# SparkFun_6DoF_ISM330DHCX_Qwiic_Micro_Alt.net
KiCad netlist of a schematic drawn in EAGLE
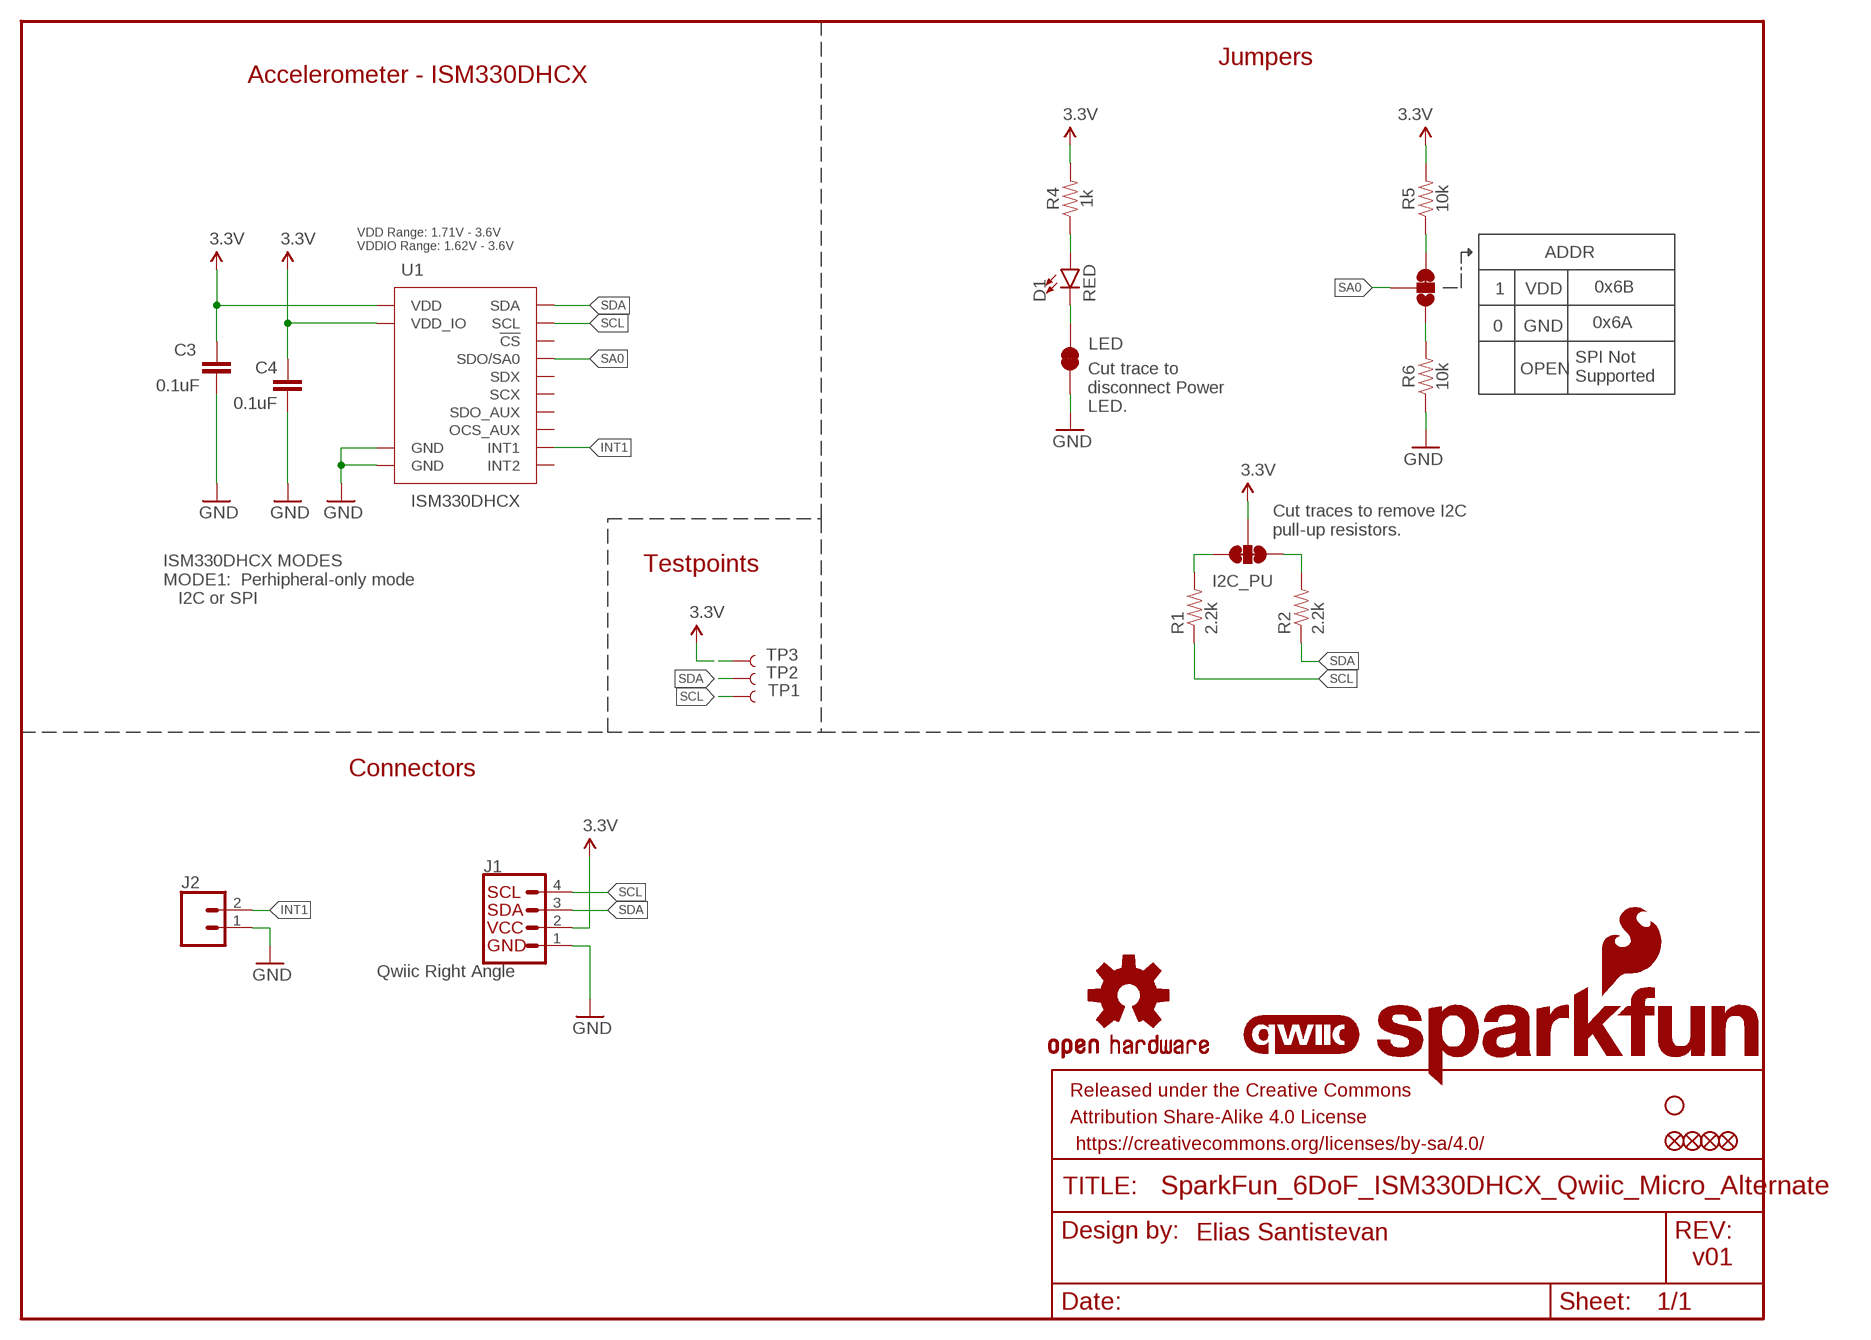
[diagram p0: schematic, sheet 1]

(export (version "E")
  (design (tool "Eeschema 10.0.6"))
  (components
    (comp (ref "ADDR")
      (value "JUMPER-SMT_3_1-NC_TRACE_SILK")
      (footprint "eagle-import:SMT-JUMPER_3_1-NC_TRACE_SILK")
      (libsource (lib "eagle-import") (part "JUMPER-SMT_3_1-NC_TRACE_SILK"))
    )
    (comp (ref "C3")
      (value "0.1uF")
      (footprint "eagle-import:0402-TIGHT")
      (libsource (lib "eagle-import") (part "0.1UF-0402T-6.3V-10%-X7R"))
    )
    (comp (ref "C4")
      (value "0.1uF")
      (footprint "eagle-import:0402-TIGHT")
      (libsource (lib "eagle-import") (part "0.1UF-0402T-6.3V-10%-X7R"))
    )
    (comp (ref "D1")
      (value "RED")
      (footprint "eagle-import:0402-TIGHT")
      (libsource (lib "eagle-import") (part "LED_0402"))
    )
    (comp (ref "FD1")
      (value "FIDUCIALUFIDUCIAL")
      (footprint "eagle-import:FIDUCIAL-MICRO")
      (libsource (lib "eagle-import") (part "FIDUCIALUFIDUCIAL"))
    )
    (comp (ref "FD2")
      (value "FIDUCIALUFIDUCIAL")
      (footprint "eagle-import:FIDUCIAL-MICRO")
      (libsource (lib "eagle-import") (part "FIDUCIALUFIDUCIAL"))
    )
    (comp (ref "FID1")
      (value "FIDUCIALUFIDUCIAL")
      (footprint "eagle-import:FIDUCIAL-MICRO")
      (libsource (lib "eagle-import") (part "FIDUCIALUFIDUCIAL"))
    )
    (comp (ref "FID2")
      (value "FIDUCIALUFIDUCIAL")
      (footprint "eagle-import:FIDUCIAL-MICRO")
      (libsource (lib "eagle-import") (part "FIDUCIALUFIDUCIAL"))
    )
    (comp (ref "FRAME1")
      (value "FRAME-LETTER")
      (footprint "eagle-import:CREATIVE_COMMONS")
      (fields (field (name "DESIGNER") "Elias Santistevan"))
      (libsource (lib "eagle-import") (part "FRAME-LETTER"))
    )
    (comp (ref "I2C_PU")
      (value "S_MODE")
      (footprint "eagle-import:SMT-JUMPER_3_2-NC_TRACE_SILK")
      (libsource (lib "eagle-import") (part "JUMPER-SMT_3_2-NC_TRACE_SILK"))
    )
    (comp (ref "J1")
      (value "Qwiic Right Angle")
      (footprint "eagle-import:JST04_1MM_RA")
      (libsource (lib "eagle-import") (part "I2C_STANDARDQWIIC"))
    )
    (comp (ref "J2")
      (value "CONN_02_1.5MM")
      (footprint "eagle-import:1X02_1.5MM_NO_SILK")
      (libsource (lib "eagle-import") (part "CONN_02_1.5MM"))
    )
    (comp (ref "LED")
      (value "JUMPER-SMT_2_NC_TRACE_SILK")
      (footprint "eagle-import:SMT-JUMPER_2_NC_TRACE_SILK")
      (libsource (lib "eagle-import") (part "JUMPER-SMT_2_NC_TRACE_SILK"))
    )
    (comp (ref "LOGO1")
      (value "QWIIC_LOGO_3MM")
      (footprint "eagle-import:QWIIC_3MM")
      (libsource (lib "eagle-import") (part "QWIIC_LOGO_3MM"))
    )
    (comp (ref "LOGO2")
      (value "OSHW-LOGOMINI")
      (footprint "eagle-import:OSHW-LOGO-MINI")
      (libsource (lib "eagle-import") (part "OSHW-LOGOMINI"))
    )
    (comp (ref "LOGO3")
      (value "SFE_LOGO_NAME_FLAMEBLANK")
      (footprint "eagle-import:BLANK")
      (libsource (lib "eagle-import") (part "SFE_LOGO_NAME_FLAMEBLANK"))
    )
    (comp (ref "R1")
      (value "2.2k")
      (footprint "eagle-import:0402-TIGHT")
      (libsource (lib "eagle-import") (part "2.2KOHM-0402T-1/16W-1%"))
    )
    (comp (ref "R2")
      (value "2.2k")
      (footprint "eagle-import:0402-TIGHT")
      (libsource (lib "eagle-import") (part "2.2KOHM-0402T-1/16W-1%"))
    )
    (comp (ref "R4")
      (value "1k")
      (footprint "eagle-import:0402-TIGHT")
      (libsource (lib "eagle-import") (part "1KOHM-0402T-1/16W-1%"))
    )
    (comp (ref "R5")
      (value "10k")
      (footprint "eagle-import:0402-TIGHT")
      (libsource (lib "eagle-import") (part "10KOHM-0402T-1/16W-1%"))
    )
    (comp (ref "R6")
      (value "10k")
      (footprint "eagle-import:0402-TIGHT")
      (libsource (lib "eagle-import") (part "10KOHM-0402T-1/16W-1%"))
    )
    (comp (ref "STANDOFF1")
      (value "STAND-OFFTIGHT")
      (footprint "eagle-import:STAND-OFF-TIGHT")
      (libsource (lib "eagle-import") (part "STAND-OFFTIGHT"))
    )
    (comp (ref "TP1")
      (value "TEST-POINT3")
      (footprint "eagle-import:PAD.03X.03")
      (libsource (lib "eagle-import") (part "TEST-POINT3"))
    )
    (comp (ref "TP2")
      (value "TEST-POINT3")
      (footprint "eagle-import:PAD.03X.03")
      (libsource (lib "eagle-import") (part "TEST-POINT3"))
    )
    (comp (ref "TP3")
      (value "TEST-POINT3")
      (footprint "eagle-import:PAD.03X.03")
      (libsource (lib "eagle-import") (part "TEST-POINT3"))
    )
    (comp (ref "U1")
      (value "ISM330DHCX")
      (footprint "eagle-import:LGA-14L")
      (libsource (lib "eagle-import") (part "ISM330DHCX"))
    )
  )
  (nets
    (net (code "1") (name "3.3V") (class "Default")
      (node (ref "C3") (pin "1") (pinfunction "1_1") (pintype "passive"))
      (node (ref "C4") (pin "1") (pinfunction "1_1") (pintype "passive"))
      (node (ref "I2C_PU") (pin "2") (pinfunction "2_2") (pintype "passive"))
      (node (ref "J1") (pin "2") (pinfunction "2_2") (pintype "power_in"))
      (node (ref "R4") (pin "2") (pinfunction "2_2") (pintype "passive"))
      (node (ref "R5") (pin "2") (pinfunction "2_2") (pintype "passive"))
      (node (ref "TP3") (pin "1") (pinfunction "1_1") (pintype "bidirectional"))
      (node (ref "U1") (pin "P5") (pinfunction "VDD_IO_P5") (pintype "power_in"))
      (node (ref "U1") (pin "P8") (pinfunction "VDD_P8") (pintype "power_in"))
    )
    (net (code "2") (name "GND") (class "Default")
      (node (ref "C3") (pin "2") (pinfunction "2_2") (pintype "passive"))
      (node (ref "C4") (pin "2") (pinfunction "2_2") (pintype "passive"))
      (node (ref "J1") (pin "1") (pinfunction "1_1") (pintype "power_in"))
      (node (ref "J2") (pin "1") (pinfunction "1_1") (pintype "passive"))
      (node (ref "LED") (pin "1") (pinfunction "1_1") (pintype "passive"))
      (node (ref "R6") (pin "1") (pinfunction "1_1") (pintype "passive"))
      (node (ref "U1") (pin "P6") (pinfunction "GND_P6") (pintype "power_in"))
      (node (ref "U1") (pin "P7") (pinfunction "GND_P7") (pintype "power_in"))
    )
    (net (code "3") (name "INT1") (class "Default")
      (node (ref "J2") (pin "2") (pinfunction "2_2") (pintype "passive"))
      (node (ref "U1") (pin "P4") (pinfunction "INT1_P4") (pintype "bidirectional"))
    )
    (net (code "4") (name "Net-(ADDR-Pad1)") (class "Default")
      (node (ref "ADDR") (pin "1") (pinfunction "1_1") (pintype "passive"))
      (node (ref "R6") (pin "2") (pinfunction "2_2") (pintype "passive"))
    )
    (net (code "5") (name "Net-(ADDR-Pad3)") (class "Default")
      (node (ref "ADDR") (pin "3") (pinfunction "3_3") (pintype "passive"))
      (node (ref "R5") (pin "1") (pinfunction "1_1") (pintype "passive"))
    )
    (net (code "6") (name "Net-(D1-PadA)") (class "Default")
      (node (ref "D1") (pin "A") (pinfunction "A_A") (pintype "passive"))
      (node (ref "R4") (pin "1") (pinfunction "1_1") (pintype "passive"))
    )
    (net (code "7") (name "Net-(D1-PadC)") (class "Default")
      (node (ref "D1") (pin "C") (pinfunction "C_C") (pintype "passive"))
      (node (ref "LED") (pin "2") (pinfunction "2_2") (pintype "passive"))
    )
    (net (code "8") (name "Net-(I2C_PU-Pad1)") (class "Default")
      (node (ref "I2C_PU") (pin "1") (pinfunction "1_1") (pintype "passive"))
      (node (ref "R1") (pin "2") (pinfunction "2_2") (pintype "passive"))
    )
    (net (code "9") (name "Net-(I2C_PU-Pad3)") (class "Default")
      (node (ref "I2C_PU") (pin "3") (pinfunction "3_3") (pintype "passive"))
      (node (ref "R2") (pin "2") (pinfunction "2_2") (pintype "passive"))
    )
    (net (code "10") (name "SA0") (class "Default")
      (node (ref "ADDR") (pin "2") (pinfunction "2_2") (pintype "passive"))
      (node (ref "U1") (pin "P1") (pinfunction "SDO/SA0_P1") (pintype "bidirectional"))
    )
    (net (code "11") (name "SCL") (class "Default")
      (node (ref "J1") (pin "4") (pinfunction "4_4") (pintype "passive"))
      (node (ref "R1") (pin "1") (pinfunction "1_1") (pintype "passive"))
      (node (ref "TP1") (pin "1") (pinfunction "1_1") (pintype "bidirectional"))
      (node (ref "U1") (pin "P13") (pinfunction "SCL_P13") (pintype "bidirectional"))
    )
    (net (code "12") (name "SDA") (class "Default")
      (node (ref "J1") (pin "3") (pinfunction "3_3") (pintype "passive"))
      (node (ref "R2") (pin "1") (pinfunction "1_1") (pintype "passive"))
      (node (ref "TP2") (pin "1") (pinfunction "1_1") (pintype "bidirectional"))
      (node (ref "U1") (pin "P14") (pinfunction "SDA_P14") (pintype "bidirectional"))
    )
    (net (code "13") (name "unconnected-(U1-INT2-PadP9)") (class "Default")
      (node (ref "U1") (pin "P9") (pinfunction "INT2_P9") (pintype "bidirectional"))
    )
    (net (code "14") (name "unconnected-(U1-OCS_AUX-PadP10)") (class "Default")
      (node (ref "U1") (pin "P10") (pinfunction "OCS_AUX_P10") (pintype "bidirectional"))
    )
    (net (code "15") (name "unconnected-(U1-SCX-PadP3)") (class "Default")
      (node (ref "U1") (pin "P3") (pinfunction "SCX_P3") (pintype "bidirectional"))
    )
    (net (code "16") (name "unconnected-(U1-SDO_AUX-PadP11)") (class "Default")
      (node (ref "U1") (pin "P11") (pinfunction "SDO_AUX_P11") (pintype "bidirectional"))
    )
    (net (code "17") (name "unconnected-(U1-SDX-PadP2)") (class "Default")
      (node (ref "U1") (pin "P2") (pinfunction "SDX_P2") (pintype "bidirectional"))
    )
    (net (code "18") (name "unconnected-(U1-~{CS}-PadP12)") (class "Default")
      (node (ref "U1") (pin "P12") (pinfunction "~{CS}_P12") (pintype "bidirectional"))
    )
  )
)
